# NC1-3-Top.net
KiCad netlist of a schematic drawn in Altium Designer
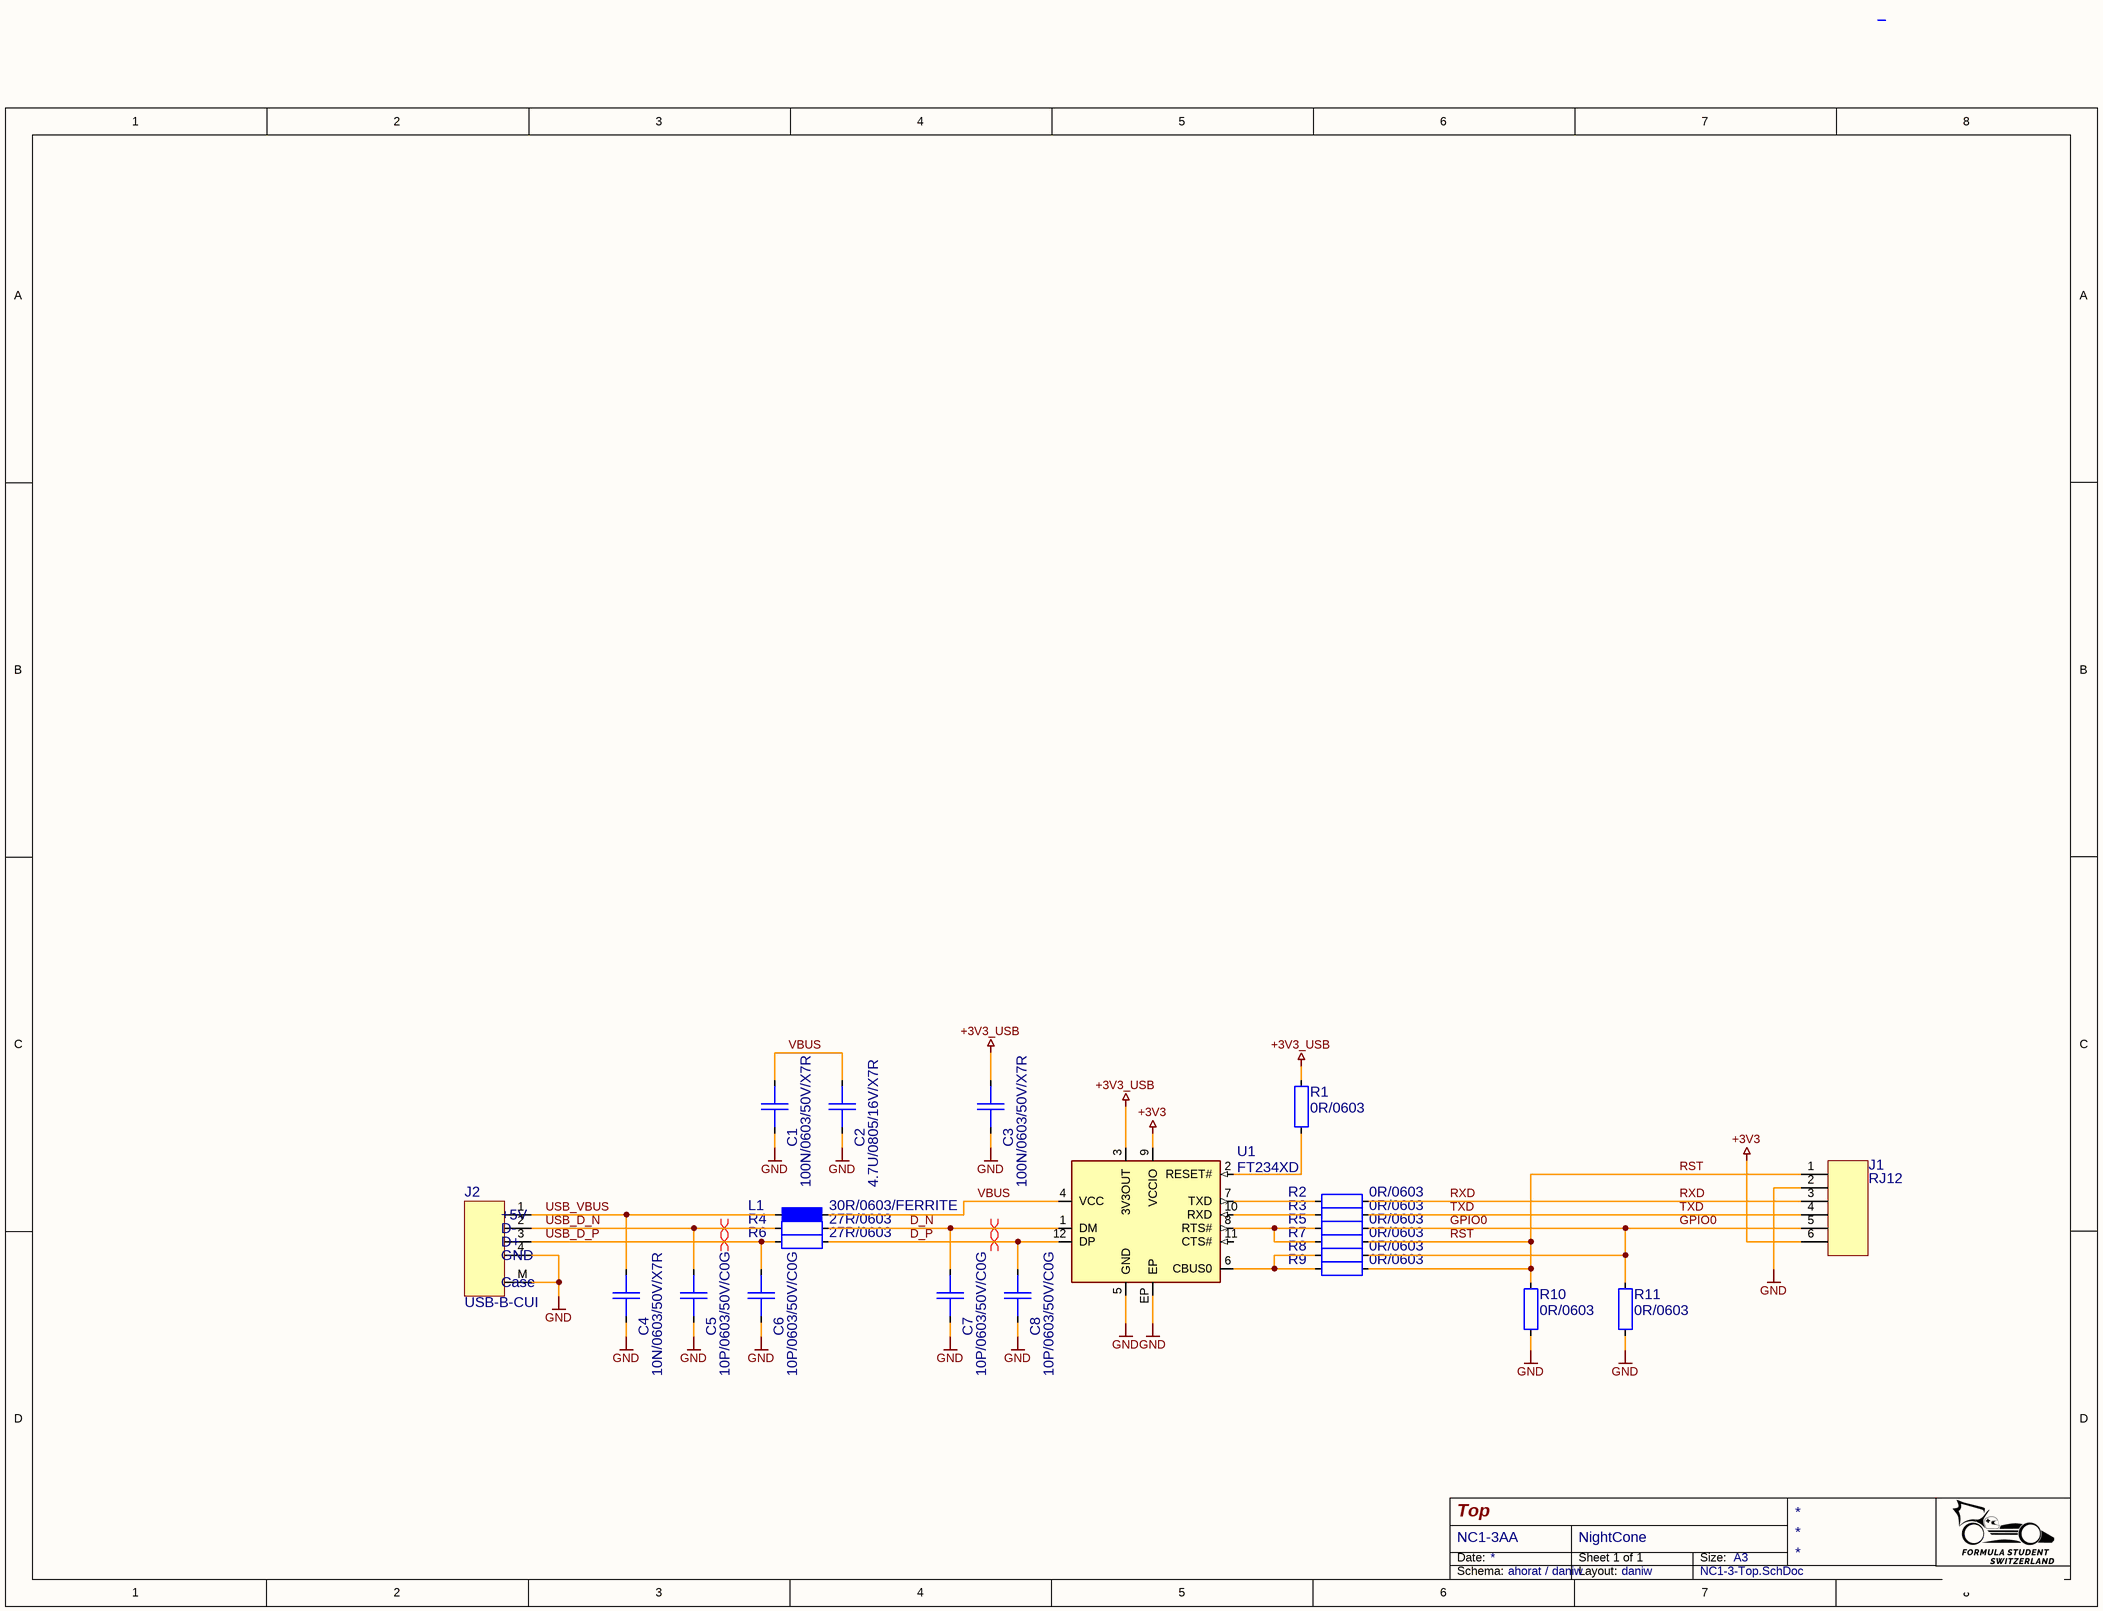
[diagram p0: NC1-3-Top.SchDoc]

(export (version "E")
  (design (tool "Eeschema 10.0.6"))
  (components
    (comp (ref "C1")
      (value "100N/0603/50V/X7R")
      (footprint "CAP0603_X7R")
      (description "CAP SM 0603 100nF 50V X7R")
      (fields (field (name "MANUFACTURER") "GENERIC"))
      (libsource (lib "daniw_altium_lib") (part "C"))
    )
    (comp (ref "C2")
      (value "4.7U/0805/16V/X7R")
      (footprint "CAP0805_X7R")
      (description "CAP SM 0805 4.7uF 16V X7R")
      (fields (field (name "MANUFACTURER") "GENERIC"))
      (libsource (lib "daniw_altium_lib") (part "C"))
    )
    (comp (ref "C3")
      (value "100N/0603/50V/X7R")
      (footprint "CAP0603_X7R")
      (description "CAP SM 0603 100nF 50V X7R")
      (fields (field (name "MANUFACTURER") "GENERIC"))
      (libsource (lib "daniw_altium_lib") (part "C"))
    )
    (comp (ref "C4")
      (value "10N/0603/50V/X7R")
      (footprint "CAP0603_X7R")
      (description "CAP SM 0603 10nF 50V X7R")
      (fields (field (name "MANUFACTURER") "GENERIC"))
      (libsource (lib "daniw_altium_lib") (part "C"))
    )
    (comp (ref "C5")
      (value "10P/0603/50V/C0G")
      (footprint "CAP0603_C0G")
      (description "CAP SM 0603 10pF 50V C0G")
      (fields (field (name "MANUFACTURER") "GENERIC"))
      (libsource (lib "daniw_altium_lib") (part "C"))
    )
    (comp (ref "C6")
      (value "10P/0603/50V/C0G")
      (footprint "CAP0603_C0G")
      (description "CAP SM 0603 10pF 50V C0G")
      (fields (field (name "MANUFACTURER") "GENERIC"))
      (libsource (lib "daniw_altium_lib") (part "C"))
    )
    (comp (ref "C7")
      (value "10P/0603/50V/C0G")
      (footprint "CAP0603_C0G")
      (description "CAP SM 0603 10pF 50V C0G")
      (fields (field (name "MANUFACTURER") "GENERIC"))
      (libsource (lib "daniw_altium_lib") (part "C"))
    )
    (comp (ref "C8")
      (value "10P/0603/50V/C0G")
      (footprint "CAP0603_C0G")
      (description "CAP SM 0603 10pF 50V C0G")
      (fields (field (name "MANUFACTURER") "GENERIC"))
      (libsource (lib "daniw_altium_lib") (part "C"))
    )
    (comp (ref "J1")
      (value "RJ12")
      (footprint "RJ12-PULSE-E5566-Q0LK22-L")
      (description "RJ12 Pulse E5566-Q0LK22-L")
      (fields (field (name "PART NUMBER") "RJ12-PULSE-E5566-Q0LK22-L") (field (name "MANUFACTURER") "Pulse"))
      (libsource (lib "daniw_altium_lib") (part "CON6"))
    )
    (comp (ref "J2")
      (value "USB-B-CUI")
      (footprint "USB-B_CUI_UJ2-BH-TH")
      (description "USB-B CUI UJ2-BH-TH")
      (fields (field (name "MANUFACTURER") "CUI"))
      (libsource (lib "daniw_altium_lib") (part "CON4-M_USB"))
    )
    (comp (ref "L1")
      (value "30R/0603/FERRITE")
      (footprint "FB0603")
      (description "30R@100MHz 5A 0603 Ferrite")
      (fields (field (name "MANUFACTURER") "GENERIC"))
      (libsource (lib "daniw_altium_lib") (part "Ferrite"))
    )
    (comp (ref "R1")
      (value "0R/0603")
      (footprint "R0603-0.40-WW")
      (description "RES SM 0603 0R")
      (fields (field (name "MANUFACTURER") "GENERIC"))
      (libsource (lib "daniw_altium_lib") (part "R"))
    )
    (comp (ref "R2")
      (value "0R/0603")
      (footprint "R0603-0.40-WW")
      (description "RES SM 0603 0R")
      (fields (field (name "MANUFACTURER") "GENERIC"))
      (libsource (lib "daniw_altium_lib") (part "R"))
    )
    (comp (ref "R3")
      (value "0R/0603")
      (footprint "R0603-0.40-WW")
      (description "RES SM 0603 0R")
      (fields (field (name "MANUFACTURER") "GENERIC"))
      (libsource (lib "daniw_altium_lib") (part "R"))
    )
    (comp (ref "R4")
      (value "27R/0603")
      (footprint "R0603-0.40-WW")
      (description "RES SM 0603 27R")
      (fields (field (name "MANUFACTURER") "GENERIC"))
      (libsource (lib "daniw_altium_lib") (part "R"))
    )
    (comp (ref "R5")
      (value "0R/0603")
      (footprint "R0603-0.40-WW")
      (description "RES SM 0603 0R")
      (fields (field (name "MANUFACTURER") "GENERIC"))
      (libsource (lib "daniw_altium_lib") (part "R"))
    )
    (comp (ref "R6")
      (value "27R/0603")
      (footprint "R0603-0.40-WW")
      (description "RES SM 0603 27R")
      (fields (field (name "MANUFACTURER") "GENERIC"))
      (libsource (lib "daniw_altium_lib") (part "R"))
    )
    (comp (ref "R7")
      (value "0R/0603")
      (footprint "R0603-0.40-WW")
      (description "RES SM 0603 0R")
      (fields (field (name "MANUFACTURER") "GENERIC"))
      (libsource (lib "daniw_altium_lib") (part "R"))
    )
    (comp (ref "R8")
      (value "0R/0603")
      (footprint "R0603-0.40-WW")
      (description "RES SM 0603 0R")
      (fields (field (name "MANUFACTURER") "GENERIC"))
      (libsource (lib "daniw_altium_lib") (part "R"))
    )
    (comp (ref "R9")
      (value "0R/0603")
      (footprint "R0603-0.40-WW")
      (description "RES SM 0603 0R")
      (fields (field (name "MANUFACTURER") "GENERIC"))
      (libsource (lib "daniw_altium_lib") (part "R"))
    )
    (comp (ref "R10")
      (value "0R/0603")
      (footprint "R0603-0.40-WW")
      (description "RES SM 0603 0R")
      (fields (field (name "MANUFACTURER") "GENERIC"))
      (libsource (lib "daniw_altium_lib") (part "R"))
    )
    (comp (ref "R11")
      (value "0R/0603")
      (footprint "R0603-0.40-WW")
      (description "RES SM 0603 0R")
      (fields (field (name "MANUFACTURER") "GENERIC"))
      (libsource (lib "daniw_altium_lib") (part "R"))
    )
    (comp (ref "U1")
      (value "FT234XD")
      (footprint "DFN045P300X300X080-12-EP160X250")
      (description "FT234XD USB TO BASIC UART IC")
      (fields (field (name "MANUFACTURER") "FTDI"))
      (libsource (lib "daniw_altium_lib") (part "FT234XD"))
    )
  )
  (nets
    (net (code "1") (name "+3V3") (class "Default")
      (node (ref "J1") (pin "6") (pintype "passive"))
      (node (ref "U1") (pin "9") (pinfunction "VCCIO_9") (pintype "passive"))
    )
    (net (code "2") (name "+3V3_USB") (class "Default")
      (node (ref "C3") (pin "1") (pinfunction "1_1") (pintype "passive"))
      (node (ref "R1") (pin "1") (pinfunction "1_1") (pintype "passive"))
      (node (ref "U1") (pin "3") (pinfunction "3V3OUT_3") (pintype "passive"))
    )
    (net (code "3") (name "/D_N") (class "Default")
      (node (ref "C7") (pin "1") (pinfunction "1_1") (pintype "passive"))
      (node (ref "R4") (pin "2") (pinfunction "2_2") (pintype "passive"))
      (node (ref "U1") (pin "1") (pinfunction "DM_1") (pintype "bidirectional"))
    )
    (net (code "4") (name "/D_P") (class "Default")
      (node (ref "C8") (pin "1") (pinfunction "1_1") (pintype "passive"))
      (node (ref "R6") (pin "2") (pinfunction "2_2") (pintype "passive"))
      (node (ref "U1") (pin "12") (pinfunction "DP_12") (pintype "bidirectional"))
    )
    (net (code "5") (name "/GPIO0") (class "Default")
      (node (ref "J1") (pin "5") (pintype "passive"))
      (node (ref "R11") (pin "2") (pinfunction "2_2") (pintype "passive"))
      (node (ref "R5") (pin "2") (pinfunction "2_2") (pintype "passive"))
      (node (ref "R8") (pin "2") (pinfunction "2_2") (pintype "passive"))
    )
    (net (code "6") (name "/RST") (class "Default")
      (node (ref "J1") (pin "1") (pintype "passive"))
      (node (ref "R10") (pin "2") (pinfunction "2_2") (pintype "passive"))
      (node (ref "R7") (pin "2") (pinfunction "2_2") (pintype "passive"))
      (node (ref "R9") (pin "2") (pinfunction "2_2") (pintype "passive"))
    )
    (net (code "7") (name "/RXD") (class "Default")
      (node (ref "J1") (pin "3") (pintype "passive"))
      (node (ref "R2") (pin "2") (pinfunction "2_2") (pintype "passive"))
    )
    (net (code "8") (name "/TXD") (class "Default")
      (node (ref "J1") (pin "4") (pintype "passive"))
      (node (ref "R3") (pin "2") (pinfunction "2_2") (pintype "passive"))
    )
    (net (code "9") (name "/USB_D_N") (class "Default")
      (node (ref "C5") (pin "1") (pinfunction "1_1") (pintype "passive"))
      (node (ref "J2") (pin "2") (pintype "passive"))
      (node (ref "R4") (pin "1") (pinfunction "1_1") (pintype "passive"))
    )
    (net (code "10") (name "/USB_D_P") (class "Default")
      (node (ref "C6") (pin "1") (pinfunction "1_1") (pintype "passive"))
      (node (ref "J2") (pin "3") (pintype "passive"))
      (node (ref "R6") (pin "1") (pinfunction "1_1") (pintype "passive"))
    )
    (net (code "11") (name "/USB_VBUS") (class "Default")
      (node (ref "C4") (pin "1") (pinfunction "1_1") (pintype "passive"))
      (node (ref "J2") (pin "1") (pintype "passive"))
      (node (ref "L1") (pin "1") (pinfunction "1_1") (pintype "passive"))
    )
    (net (code "12") (name "/VBUS") (class "Default")
      (node (ref "C1") (pin "1") (pinfunction "1_1") (pintype "passive"))
      (node (ref "C2") (pin "1") (pinfunction "1_1") (pintype "passive"))
      (node (ref "L1") (pin "2") (pinfunction "2_2") (pintype "passive"))
      (node (ref "U1") (pin "4") (pinfunction "VCC_4") (pintype "passive"))
    )
    (net (code "13") (name "GND") (class "Default")
      (node (ref "C1") (pin "2") (pinfunction "2_2") (pintype "passive"))
      (node (ref "C2") (pin "2") (pinfunction "2_2") (pintype "passive"))
      (node (ref "C3") (pin "2") (pinfunction "2_2") (pintype "passive"))
      (node (ref "C4") (pin "2") (pinfunction "2_2") (pintype "passive"))
      (node (ref "C5") (pin "2") (pinfunction "2_2") (pintype "passive"))
      (node (ref "C6") (pin "2") (pinfunction "2_2") (pintype "passive"))
      (node (ref "C7") (pin "2") (pinfunction "2_2") (pintype "passive"))
      (node (ref "C8") (pin "2") (pinfunction "2_2") (pintype "passive"))
      (node (ref "J1") (pin "2") (pintype "passive"))
      (node (ref "J2") (pin "4") (pintype "passive"))
      (node (ref "J2") (pin "M") (pintype "passive"))
      (node (ref "R10") (pin "1") (pinfunction "1_1") (pintype "passive"))
      (node (ref "R11") (pin "1") (pinfunction "1_1") (pintype "passive"))
      (node (ref "U1") (pin "5") (pinfunction "GND_5") (pintype "passive"))
      (node (ref "U1") (pin "EP") (pinfunction "EP_EP") (pintype "passive"))
    )
    (net (code "14") (name "Net-(U1-CBUS0)") (class "Default")
      (node (ref "R8") (pin "1") (pinfunction "1_1") (pintype "passive"))
      (node (ref "R9") (pin "1") (pinfunction "1_1") (pintype "passive"))
      (node (ref "U1") (pin "6") (pinfunction "CBUS0_6") (pintype "bidirectional"))
    )
    (net (code "15") (name "Net-(U1-RESET#)") (class "Default")
      (node (ref "R1") (pin "2") (pinfunction "2_2") (pintype "passive"))
      (node (ref "U1") (pin "2") (pinfunction "RESET#_2") (pintype "input"))
    )
    (net (code "16") (name "Net-(U1-RTS#)") (class "Default")
      (node (ref "R5") (pin "1") (pinfunction "1_1") (pintype "passive"))
      (node (ref "R7") (pin "1") (pinfunction "1_1") (pintype "passive"))
      (node (ref "U1") (pin "8") (pinfunction "RTS#_8") (pintype "output"))
    )
    (net (code "17") (name "Net-(U1-RXD)") (class "Default")
      (node (ref "R3") (pin "1") (pinfunction "1_1") (pintype "passive"))
      (node (ref "U1") (pin "10") (pinfunction "RXD_10") (pintype "input"))
    )
    (net (code "18") (name "Net-(U1-TXD)") (class "Default")
      (node (ref "R2") (pin "1") (pinfunction "1_1") (pintype "passive"))
      (node (ref "U1") (pin "7") (pinfunction "TXD_7") (pintype "output"))
    )
    (net (code "19") (name "unconnected-(U1-CTS#-Pad11)") (class "Default")
      (node (ref "U1") (pin "11") (pinfunction "CTS#_11") (pintype "input"))
    )
  )
)
